# TouringMachineB1.net
KiCad netlist of a schematic drawn in EAGLE
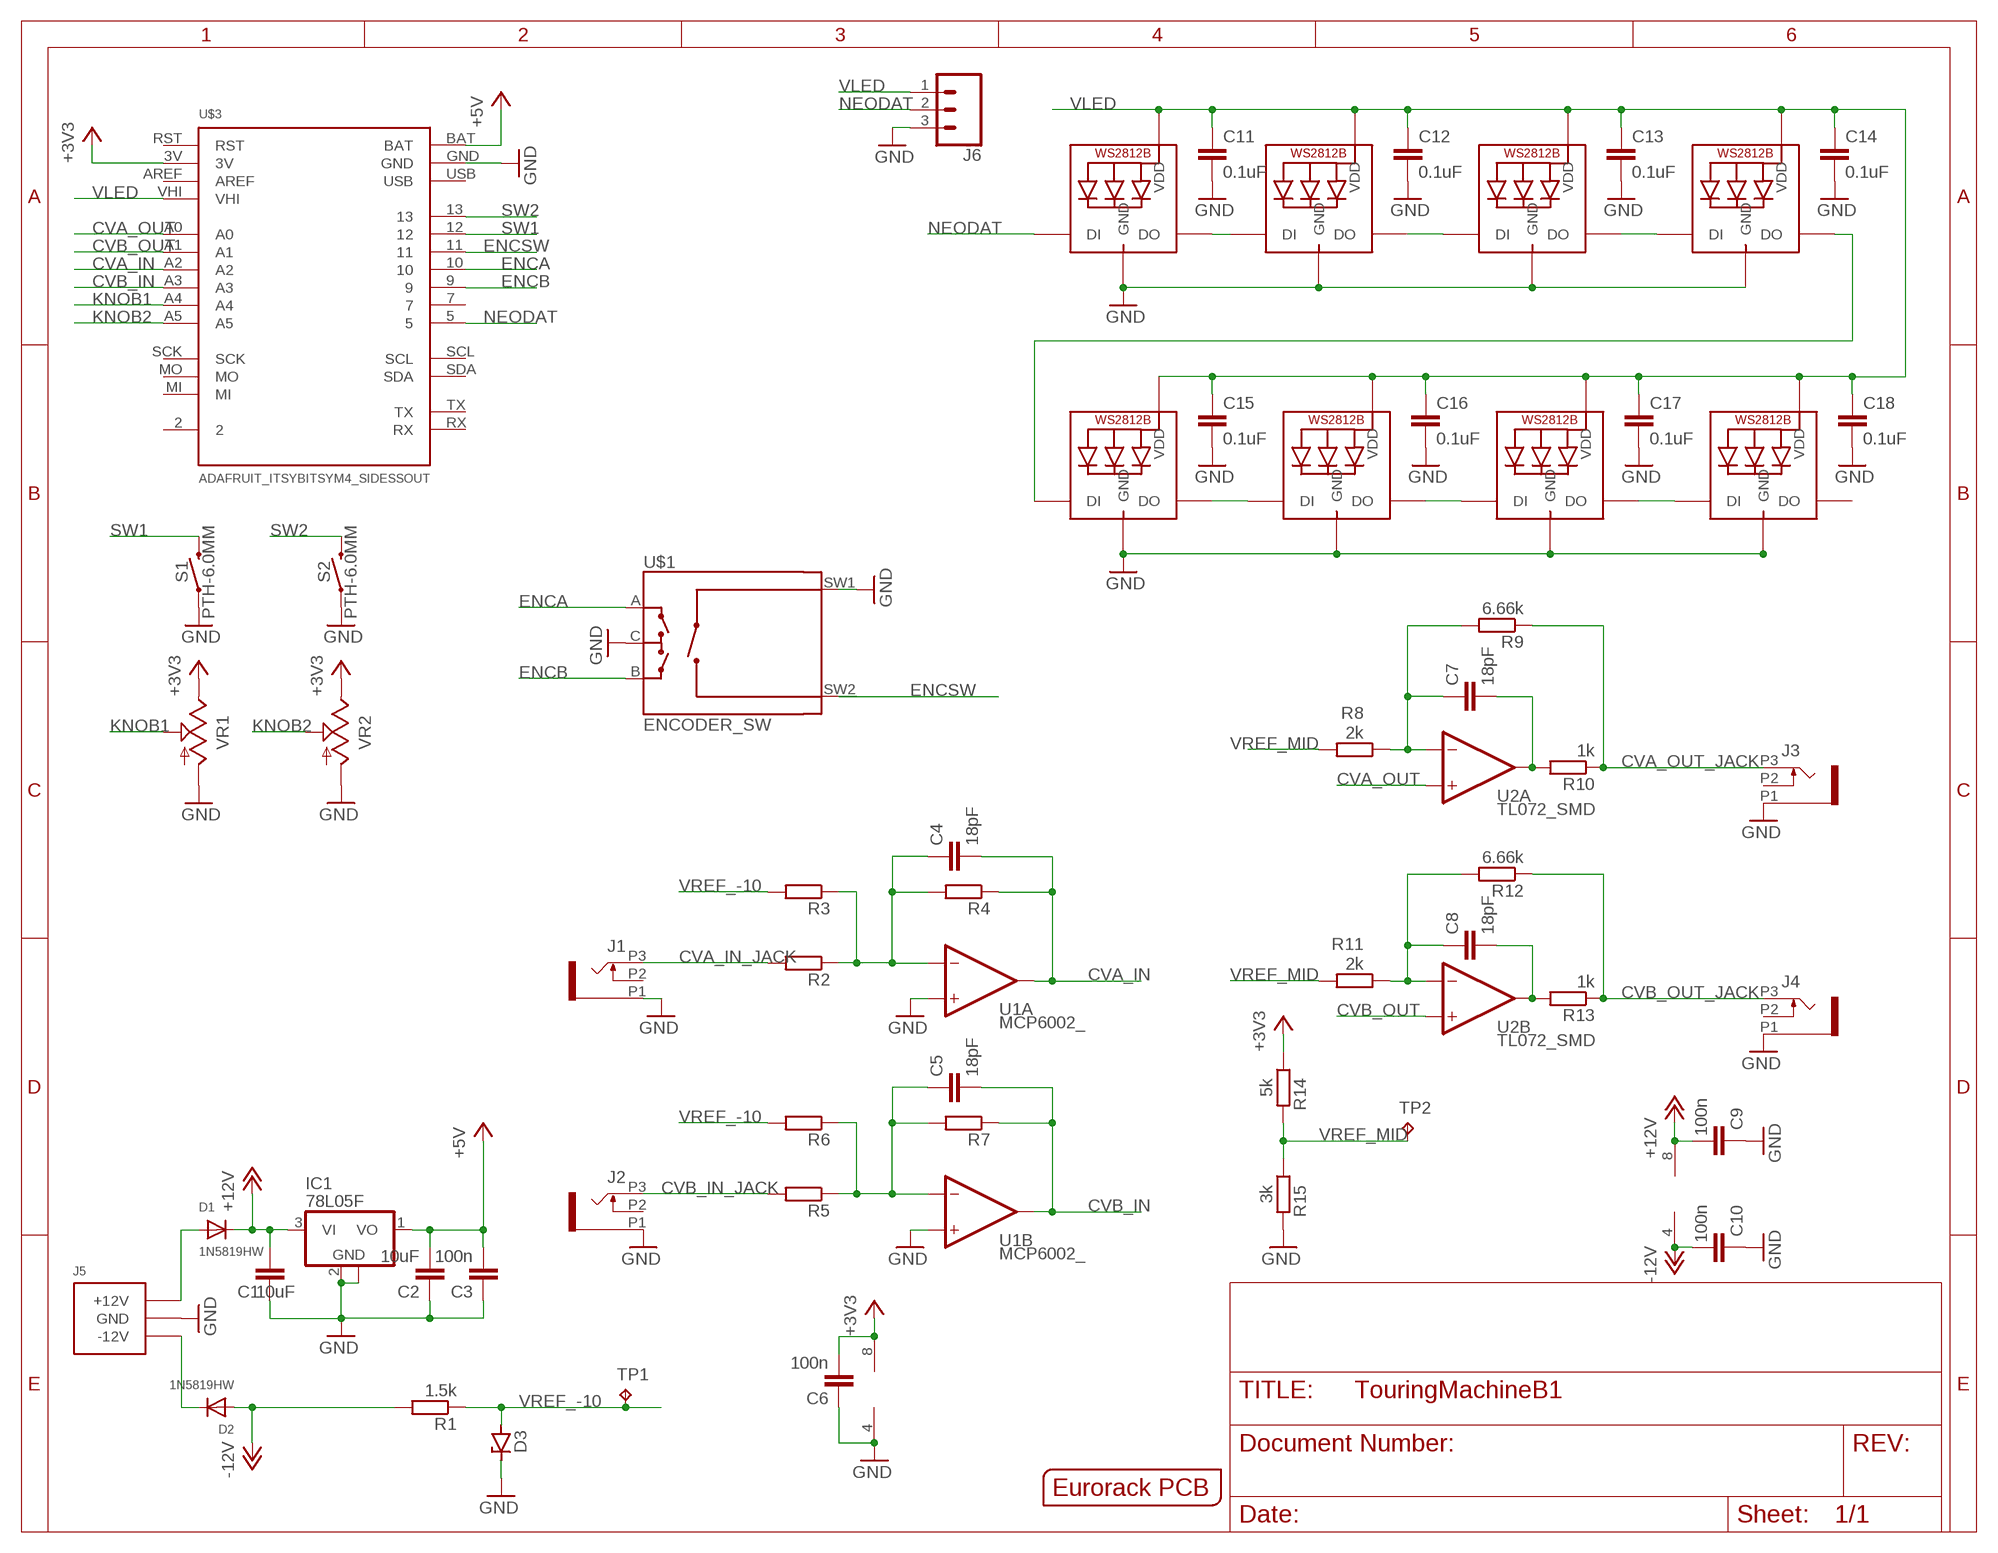
[diagram p0: schematic, sheet 1]

(export (version "E")
  (design (tool "Eeschema 10.0.6"))
  (components
    (comp (ref "C1")
      (value "10uF")
      (footprint "eagle-import:C0603")
      (libsource (lib "eagle-import") (part "C-EUC0603"))
    )
    (comp (ref "C2")
      (value "10uF")
      (footprint "eagle-import:C0603")
      (libsource (lib "eagle-import") (part "C-EUC0603"))
    )
    (comp (ref "C3")
      (value "100n")
      (footprint "eagle-import:C0603")
      (libsource (lib "eagle-import") (part "C-EUC0603"))
    )
    (comp (ref "C4")
      (value "18pF")
      (footprint "eagle-import:C0603")
      (libsource (lib "eagle-import") (part "C-EUC0603"))
    )
    (comp (ref "C5")
      (value "18pF")
      (footprint "eagle-import:C0603")
      (libsource (lib "eagle-import") (part "C-EUC0603"))
    )
    (comp (ref "C6")
      (value "100n")
      (footprint "eagle-import:C0603")
      (libsource (lib "eagle-import") (part "C-EUC0603"))
    )
    (comp (ref "C7")
      (value "18pF")
      (footprint "eagle-import:C0603")
      (libsource (lib "eagle-import") (part "C-EUC0603"))
    )
    (comp (ref "C8")
      (value "18pF")
      (footprint "eagle-import:C0603")
      (libsource (lib "eagle-import") (part "C-EUC0603"))
    )
    (comp (ref "C9")
      (value "100n")
      (footprint "eagle-import:C0603")
      (libsource (lib "eagle-import") (part "C-EUC0603"))
    )
    (comp (ref "C10")
      (value "100n")
      (footprint "eagle-import:C0603")
      (libsource (lib "eagle-import") (part "C-EUC0603"))
    )
    (comp (ref "C11")
      (value "0.1uF")
      (footprint "eagle-import:C0603")
      (libsource (lib "eagle-import") (part "C-EUC0603"))
    )
    (comp (ref "C12")
      (value "0.1uF")
      (footprint "eagle-import:C0603")
      (libsource (lib "eagle-import") (part "C-EUC0603"))
    )
    (comp (ref "C13")
      (value "0.1uF")
      (footprint "eagle-import:C0603")
      (libsource (lib "eagle-import") (part "C-EUC0603"))
    )
    (comp (ref "C14")
      (value "0.1uF")
      (footprint "eagle-import:C0603")
      (libsource (lib "eagle-import") (part "C-EUC0603"))
    )
    (comp (ref "C15")
      (value "0.1uF")
      (footprint "eagle-import:C0603")
      (libsource (lib "eagle-import") (part "C-EUC0603"))
    )
    (comp (ref "C16")
      (value "0.1uF")
      (footprint "eagle-import:C0603")
      (libsource (lib "eagle-import") (part "C-EUC0603"))
    )
    (comp (ref "C17")
      (value "0.1uF")
      (footprint "eagle-import:C0603")
      (libsource (lib "eagle-import") (part "C-EUC0603"))
    )
    (comp (ref "C18")
      (value "0.1uF")
      (footprint "eagle-import:C0603")
      (libsource (lib "eagle-import") (part "C-EUC0603"))
    )
    (comp (ref "D1")
      (value "1N5819HW")
      (footprint "eagle-import:SOD-123")
      (libsource (lib "eagle-import") (part "DIODESOD-123"))
    )
    (comp (ref "D2")
      (value "1N5819HW")
      (footprint "eagle-import:SOD-123")
      (libsource (lib "eagle-import") (part "DIODESOD-123"))
    )
    (comp (ref "D3")
      (value "ZENER-DIODESOT23")
      (footprint "eagle-import:SOT23")
      (libsource (lib "eagle-import") (part "ZENER-DIODESOT23"))
    )
    (comp (ref "IC1")
      (value "78L05F")
      (footprint "eagle-import:SOT89")
      (libsource (lib "eagle-import") (part "78LF05"))
    )
    (comp (ref "J1")
      (value "PJ301_THONKICONN6")
      (footprint "eagle-import:WQP_PJ_301M6")
      (libsource (lib "eagle-import") (part "PJ301_THONKICONN6"))
    )
    (comp (ref "J2")
      (value "PJ301_THONKICONN6")
      (footprint "eagle-import:WQP_PJ_301M6")
      (libsource (lib "eagle-import") (part "PJ301_THONKICONN6"))
    )
    (comp (ref "J3")
      (value "PJ301_THONKICONN6")
      (footprint "eagle-import:WQP_PJ_301M6")
      (libsource (lib "eagle-import") (part "PJ301_THONKICONN6"))
    )
    (comp (ref "J4")
      (value "PJ301_THONKICONN6")
      (footprint "eagle-import:WQP_PJ_301M6")
      (libsource (lib "eagle-import") (part "PJ301_THONKICONN6"))
    )
    (comp (ref "J5")
      (value "POWER_SIMPLE10-OTHERSIDE")
      (footprint "eagle-import:POWER_10_LABELSOTHERSIDE")
      (libsource (lib "eagle-import") (part "POWER_SIMPLE10-OTHERSIDE"))
    )
    (comp (ref "J6")
      (value "CONN_03")
      (footprint "eagle-import:1X03")
      (libsource (lib "eagle-import") (part "CONN_03"))
    )
    (comp (ref "LED1")
      (value "WS2812B5050")
      (footprint "eagle-import:WS2812B")
      (libsource (lib "eagle-import") (part "WS2812B5050"))
    )
    (comp (ref "LED2")
      (value "WS2812B5050")
      (footprint "eagle-import:WS2812B")
      (libsource (lib "eagle-import") (part "WS2812B5050"))
    )
    (comp (ref "LED3")
      (value "WS2812B5050")
      (footprint "eagle-import:WS2812B")
      (libsource (lib "eagle-import") (part "WS2812B5050"))
    )
    (comp (ref "LED4")
      (value "WS2812B5050")
      (footprint "eagle-import:WS2812B")
      (libsource (lib "eagle-import") (part "WS2812B5050"))
    )
    (comp (ref "LED5")
      (value "WS2812B5050")
      (footprint "eagle-import:WS2812B")
      (libsource (lib "eagle-import") (part "WS2812B5050"))
    )
    (comp (ref "LED6")
      (value "WS2812B5050")
      (footprint "eagle-import:WS2812B")
      (libsource (lib "eagle-import") (part "WS2812B5050"))
    )
    (comp (ref "LED7")
      (value "WS2812B5050")
      (footprint "eagle-import:WS2812B")
      (libsource (lib "eagle-import") (part "WS2812B5050"))
    )
    (comp (ref "LED8")
      (value "WS2812B5050")
      (footprint "eagle-import:WS2812B")
      (libsource (lib "eagle-import") (part "WS2812B5050"))
    )
    (comp (ref "PCB1")
      (value "EURORACK_PCB6HP")
      (footprint "eagle-import:EURORACK6HPPCB")
      (libsource (lib "eagle-import") (part "EURORACK_PCB6HP"))
    )
    (comp (ref "R1")
      (value "1.5k")
      (footprint "eagle-import:R0603")
      (libsource (lib "eagle-import") (part "R-EU_R0603"))
    )
    (comp (ref "R2")
      (value "R-EU_R0603")
      (footprint "eagle-import:R0603")
      (libsource (lib "eagle-import") (part "R-EU_R0603"))
    )
    (comp (ref "R3")
      (value "R-EU_R0603")
      (footprint "eagle-import:R0603")
      (libsource (lib "eagle-import") (part "R-EU_R0603"))
    )
    (comp (ref "R4")
      (value "R-EU_R0603")
      (footprint "eagle-import:R0603")
      (libsource (lib "eagle-import") (part "R-EU_R0603"))
    )
    (comp (ref "R5")
      (value "R-EU_R0603")
      (footprint "eagle-import:R0603")
      (libsource (lib "eagle-import") (part "R-EU_R0603"))
    )
    (comp (ref "R6")
      (value "R-EU_R0603")
      (footprint "eagle-import:R0603")
      (libsource (lib "eagle-import") (part "R-EU_R0603"))
    )
    (comp (ref "R7")
      (value "R-EU_R0603")
      (footprint "eagle-import:R0603")
      (libsource (lib "eagle-import") (part "R-EU_R0603"))
    )
    (comp (ref "R8")
      (value "2k")
      (footprint "eagle-import:R0603")
      (libsource (lib "eagle-import") (part "R-EU_R0603"))
    )
    (comp (ref "R9")
      (value "6.66k")
      (footprint "eagle-import:R0603")
      (libsource (lib "eagle-import") (part "R-EU_R0603"))
    )
    (comp (ref "R10")
      (value "1k")
      (footprint "eagle-import:R0603")
      (libsource (lib "eagle-import") (part "R-EU_R0603"))
    )
    (comp (ref "R11")
      (value "2k")
      (footprint "eagle-import:R0603")
      (libsource (lib "eagle-import") (part "R-EU_R0603"))
    )
    (comp (ref "R12")
      (value "6.66k")
      (footprint "eagle-import:R0603")
      (libsource (lib "eagle-import") (part "R-EU_R0603"))
    )
    (comp (ref "R13")
      (value "1k")
      (footprint "eagle-import:R0603")
      (libsource (lib "eagle-import") (part "R-EU_R0603"))
    )
    (comp (ref "R14")
      (value "5k")
      (footprint "eagle-import:R0603")
      (libsource (lib "eagle-import") (part "R-EU_R0603"))
    )
    (comp (ref "R15")
      (value "3k")
      (footprint "eagle-import:R0603")
      (libsource (lib "eagle-import") (part "R-EU_R0603"))
    )
    (comp (ref "S1")
      (value "PTH-6.0MM")
      (footprint "eagle-import:TACTILE_SWITCH_PTH_6.0MM")
      (libsource (lib "eagle-import") (part "MOMENTARY-SWITCH-SPST-PTH-6.0MM"))
    )
    (comp (ref "S2")
      (value "PTH-6.0MM")
      (footprint "eagle-import:TACTILE_SWITCH_PTH_6.0MM")
      (libsource (lib "eagle-import") (part "MOMENTARY-SWITCH-SPST-PTH-6.0MM"))
    )
    (comp (ref "TP1")
      (value "TPTP15R")
      (footprint "eagle-import:TP15R")
      (libsource (lib "eagle-import") (part "TPTP15R"))
    )
    (comp (ref "TP2")
      (value "TPTP15R")
      (footprint "eagle-import:TP15R")
      (libsource (lib "eagle-import") (part "TPTP15R"))
    )
    (comp (ref "U$1")
      (value "ENCODER_SW")
      (footprint "eagle-import:ENCODER_SW")
      (libsource (lib "eagle-import") (part "ENCODER_SW"))
    )
    (comp (ref "U$3")
      (value "ADAFRUIT_ITSYBITSYM4_SIDESSOUT")
      (footprint "eagle-import:ADAFRUIT_ITSYBITSYM4_SIDESOUT")
      (libsource (lib "eagle-import") (part "ADAFRUIT_ITSYBITSYM4_SIDESSOUT"))
    )
    (comp (ref "U1")
      (value "MCP6002_")
      (footprint "eagle-import:SO08")
      (libsource (lib "eagle-import") (part "MCP6002_"))
    )
    (comp (ref "U2")
      (value "TL072_SMD")
      (footprint "eagle-import:SO08")
      (libsource (lib "eagle-import") (part "TL072_SMD"))
    )
    (comp (ref "VR1")
      (value "9MM_SNAP-IN_POT_")
      (footprint "eagle-import:9MM_SNAP-IN_POT")
      (libsource (lib "eagle-import") (part "9MM_SNAP-IN_POT_"))
    )
    (comp (ref "VR2")
      (value "9MM_SNAP-IN_POT_")
      (footprint "eagle-import:9MM_SNAP-IN_POT")
      (libsource (lib "eagle-import") (part "9MM_SNAP-IN_POT_"))
    )
  )
  (nets
    (net (code "1") (name "+3V3") (class "Default")
      (node (ref "C6") (pin "2") (pinfunction "2_2") (pintype "passive"))
      (node (ref "R14") (pin "1") (pinfunction "1_1") (pintype "passive"))
      (node (ref "U$3") (pin "3V") (pinfunction "3V_3V") (pintype "bidirectional"))
      (node (ref "U1") (pin "8") (pinfunction "V+_8") (pintype "power_in"))
      (node (ref "VR1") (pin "3") (pinfunction "E_3") (pintype "passive"))
      (node (ref "VR2") (pin "3") (pinfunction "E_3") (pintype "passive"))
    )
    (net (code "2") (name "+5V") (class "Default")
      (node (ref "C2") (pin "2") (pinfunction "2_2") (pintype "passive"))
      (node (ref "C3") (pin "2") (pinfunction "2_2") (pintype "passive"))
      (node (ref "IC1") (pin "1") (pinfunction "VO_1") (pintype "passive"))
      (node (ref "U$3") (pin "BAT") (pinfunction "BAT_BAT") (pintype "bidirectional"))
    )
    (net (code "3") (name "+12V") (class "Default")
      (node (ref "C1") (pin "2") (pinfunction "2_2") (pintype "passive"))
      (node (ref "C9") (pin "2") (pinfunction "2_2") (pintype "passive"))
      (node (ref "D1") (pin "C") (pinfunction "C_C") (pintype "passive"))
      (node (ref "IC1") (pin "3") (pinfunction "VI_3") (pintype "input"))
      (node (ref "U2") (pin "8") (pinfunction "V+_8") (pintype "power_in"))
    )
    (net (code "4") (name "-12V") (class "Default")
      (node (ref "C10") (pin "2") (pinfunction "2_2") (pintype "passive"))
      (node (ref "D2") (pin "A") (pinfunction "A_A") (pintype "passive"))
      (node (ref "R1") (pin "2") (pinfunction "2_2") (pintype "passive"))
      (node (ref "U2") (pin "4") (pinfunction "V-_4") (pintype "power_in"))
    )
    (net (code "5") (name "/CVA_IN") (class "Default")
      (node (ref "C4") (pin "2") (pinfunction "2_2") (pintype "passive"))
      (node (ref "R4") (pin "1") (pinfunction "1_1") (pintype "passive"))
      (node (ref "U$3") (pin "A2") (pinfunction "A2_A2") (pintype "bidirectional"))
      (node (ref "U1") (pin "1") (pinfunction "OUT_1") (pintype "output"))
    )
    (net (code "6") (name "/CVA_IN_JACK") (class "Default")
      (node (ref "J1") (pin "P3") (pinfunction "3_P3") (pintype "passive"))
      (node (ref "R2") (pin "2") (pinfunction "2_2") (pintype "passive"))
    )
    (net (code "7") (name "/CVA_OUT") (class "Default")
      (node (ref "U$3") (pin "A0") (pinfunction "A0_A0") (pintype "bidirectional"))
      (node (ref "U2") (pin "3") (pinfunction "+IN_3") (pintype "input"))
    )
    (net (code "8") (name "/CVA_OUT_JACK") (class "Default")
      (node (ref "J3") (pin "P3") (pinfunction "3_P3") (pintype "passive"))
      (node (ref "R10") (pin "1") (pinfunction "1_1") (pintype "passive"))
      (node (ref "R9") (pin "1") (pinfunction "1_1") (pintype "passive"))
    )
    (net (code "9") (name "/CVB_IN") (class "Default")
      (node (ref "C5") (pin "2") (pinfunction "2_2") (pintype "passive"))
      (node (ref "R7") (pin "1") (pinfunction "1_1") (pintype "passive"))
      (node (ref "U$3") (pin "A3") (pinfunction "A3_A3") (pintype "bidirectional"))
      (node (ref "U1") (pin "7") (pinfunction "OUT_7") (pintype "output"))
    )
    (net (code "10") (name "/CVB_IN_JACK") (class "Default")
      (node (ref "J2") (pin "P3") (pinfunction "3_P3") (pintype "passive"))
      (node (ref "R5") (pin "2") (pinfunction "2_2") (pintype "passive"))
    )
    (net (code "11") (name "/CVB_OUT") (class "Default")
      (node (ref "U$3") (pin "A1") (pinfunction "A1_A1") (pintype "bidirectional"))
      (node (ref "U2") (pin "5") (pinfunction "+IN_5") (pintype "input"))
    )
    (net (code "12") (name "/CVB_OUT_JACK") (class "Default")
      (node (ref "J4") (pin "P3") (pinfunction "3_P3") (pintype "passive"))
      (node (ref "R12") (pin "1") (pinfunction "1_1") (pintype "passive"))
      (node (ref "R13") (pin "1") (pinfunction "1_1") (pintype "passive"))
    )
    (net (code "13") (name "/ENCA") (class "Default")
      (node (ref "U$1") (pin "A") (pinfunction "A_A") (pintype "bidirectional"))
      (node (ref "U$3") (pin "10") (pinfunction "10_10") (pintype "bidirectional"))
    )
    (net (code "14") (name "/ENCB") (class "Default")
      (node (ref "U$1") (pin "B") (pinfunction "B_B") (pintype "bidirectional"))
      (node (ref "U$3") (pin "9") (pinfunction "9_9") (pintype "bidirectional"))
    )
    (net (code "15") (name "/ENCSW") (class "Default")
      (node (ref "U$1") (pin "SW2") (pinfunction "SW2_SW2") (pintype "passive"))
      (node (ref "U$3") (pin "11") (pinfunction "11_11") (pintype "bidirectional"))
    )
    (net (code "16") (name "/KNOB1") (class "Default")
      (node (ref "U$3") (pin "A4") (pinfunction "A4_A4") (pintype "bidirectional"))
      (node (ref "VR1") (pin "2") (pinfunction "S_2") (pintype "passive"))
    )
    (net (code "17") (name "/KNOB2") (class "Default")
      (node (ref "U$3") (pin "A5") (pinfunction "A5_A5") (pintype "bidirectional"))
      (node (ref "VR2") (pin "2") (pinfunction "S_2") (pintype "passive"))
    )
    (net (code "18") (name "/NEODAT") (class "Default")
      (node (ref "J6") (pin "2") (pinfunction "2_2") (pintype "passive"))
      (node (ref "LED1") (pin "4-DIN") (pinfunction "DI_4-DIN") (pintype "input"))
      (node (ref "U$3") (pin "5") (pinfunction "5_5") (pintype "bidirectional"))
    )
    (net (code "19") (name "/SW1") (class "Default")
      (node (ref "S1") (pin "3") (pinfunction "2_3") (pintype "passive"))
      (node (ref "U$3") (pin "12") (pinfunction "12_12") (pintype "bidirectional"))
    )
    (net (code "20") (name "/SW2") (class "Default")
      (node (ref "S2") (pin "3") (pinfunction "2_3") (pintype "passive"))
      (node (ref "U$3") (pin "13") (pinfunction "13_13") (pintype "bidirectional"))
    )
    (net (code "21") (name "/VLED") (class "Default")
      (node (ref "C11") (pin "1") (pinfunction "1_1") (pintype "passive"))
      (node (ref "C12") (pin "1") (pinfunction "1_1") (pintype "passive"))
      (node (ref "C13") (pin "1") (pinfunction "1_1") (pintype "passive"))
      (node (ref "C14") (pin "1") (pinfunction "1_1") (pintype "passive"))
      (node (ref "C15") (pin "1") (pinfunction "1_1") (pintype "passive"))
      (node (ref "C16") (pin "1") (pinfunction "1_1") (pintype "passive"))
      (node (ref "C17") (pin "1") (pinfunction "1_1") (pintype "passive"))
      (node (ref "C18") (pin "1") (pinfunction "1_1") (pintype "passive"))
      (node (ref "J6") (pin "1") (pinfunction "1_1") (pintype "passive"))
      (node (ref "LED1") (pin "1-VDD") (pinfunction "VDD_1-VDD") (pintype "power_in"))
      (node (ref "LED2") (pin "1-VDD") (pinfunction "VDD_1-VDD") (pintype "power_in"))
      (node (ref "LED3") (pin "1-VDD") (pinfunction "VDD_1-VDD") (pintype "power_in"))
      (node (ref "LED4") (pin "1-VDD") (pinfunction "VDD_1-VDD") (pintype "power_in"))
      (node (ref "LED5") (pin "1-VDD") (pinfunction "VDD_1-VDD") (pintype "power_in"))
      (node (ref "LED6") (pin "1-VDD") (pinfunction "VDD_1-VDD") (pintype "power_in"))
      (node (ref "LED7") (pin "1-VDD") (pinfunction "VDD_1-VDD") (pintype "power_in"))
      (node (ref "LED8") (pin "1-VDD") (pinfunction "VDD_1-VDD") (pintype "power_in"))
      (node (ref "U$3") (pin "VHI") (pinfunction "VHI_VHI") (pintype "bidirectional"))
    )
    (net (code "22") (name "/VREF_-10") (class "Default")
      (node (ref "D3") (pin "1") (pinfunction "A_1") (pintype "passive"))
      (node (ref "R1") (pin "1") (pinfunction "1_1") (pintype "passive"))
      (node (ref "R3") (pin "2") (pinfunction "2_2") (pintype "passive"))
      (node (ref "R6") (pin "2") (pinfunction "2_2") (pintype "passive"))
      (node (ref "TP1") (pin "TP") (pinfunction "TP_TP") (pintype "input"))
    )
    (net (code "23") (name "/VREF_MID") (class "Default")
      (node (ref "R11") (pin "2") (pinfunction "2_2") (pintype "passive"))
      (node (ref "R14") (pin "2") (pinfunction "2_2") (pintype "passive"))
      (node (ref "R15") (pin "1") (pinfunction "1_1") (pintype "passive"))
      (node (ref "R8") (pin "2") (pinfunction "2_2") (pintype "passive"))
      (node (ref "TP2") (pin "TP") (pinfunction "TP_TP") (pintype "input"))
    )
    (net (code "24") (name "GND") (class "Default")
      (node (ref "C1") (pin "1") (pinfunction "1_1") (pintype "passive"))
      (node (ref "C10") (pin "1") (pinfunction "1_1") (pintype "passive"))
      (node (ref "C11") (pin "2") (pinfunction "2_2") (pintype "passive"))
      (node (ref "C12") (pin "2") (pinfunction "2_2") (pintype "passive"))
      (node (ref "C13") (pin "2") (pinfunction "2_2") (pintype "passive"))
      (node (ref "C14") (pin "2") (pinfunction "2_2") (pintype "passive"))
      (node (ref "C15") (pin "2") (pinfunction "2_2") (pintype "passive"))
      (node (ref "C16") (pin "2") (pinfunction "2_2") (pintype "passive"))
      (node (ref "C17") (pin "2") (pinfunction "2_2") (pintype "passive"))
      (node (ref "C18") (pin "2") (pinfunction "2_2") (pintype "passive"))
      (node (ref "C2") (pin "1") (pinfunction "1_1") (pintype "passive"))
      (node (ref "C3") (pin "1") (pinfunction "1_1") (pintype "passive"))
      (node (ref "C6") (pin "1") (pinfunction "1_1") (pintype "passive"))
      (node (ref "C9") (pin "1") (pinfunction "1_1") (pintype "passive"))
      (node (ref "D3") (pin "3") (pinfunction "C_3") (pintype "passive"))
      (node (ref "IC1") (pin "2") (pinfunction "GND_2") (pintype "passive"))
      (node (ref "IC1") (pin "2@1") (pinfunction "GND_2@1") (pintype "passive"))
      (node (ref "J1") (pin "P1") (pinfunction "1_P1") (pintype "passive"))
      (node (ref "J2") (pin "P1") (pinfunction "1_P1") (pintype "passive"))
      (node (ref "J3") (pin "P1") (pinfunction "1_P1") (pintype "passive"))
      (node (ref "J4") (pin "P1") (pinfunction "1_P1") (pintype "passive"))
      (node (ref "J5") (pin "3") (pinfunction "GND_3") (pintype "bidirectional"))
      (node (ref "J5") (pin "4") (pinfunction "GND_4") (pintype "bidirectional"))
      (node (ref "J5") (pin "5") (pinfunction "GND_5") (pintype "bidirectional"))
      (node (ref "J5") (pin "6") (pinfunction "GND_6") (pintype "bidirectional"))
      (node (ref "J5") (pin "7") (pinfunction "GND_7") (pintype "bidirectional"))
      (node (ref "J5") (pin "8") (pinfunction "GND_8") (pintype "bidirectional"))
      (node (ref "J6") (pin "3") (pinfunction "3_3") (pintype "passive"))
      (node (ref "LED1") (pin "3-GND") (pinfunction "GND_3-GND") (pintype "power_in"))
      (node (ref "LED2") (pin "3-GND") (pinfunction "GND_3-GND") (pintype "power_in"))
      (node (ref "LED3") (pin "3-GND") (pinfunction "GND_3-GND") (pintype "power_in"))
      (node (ref "LED4") (pin "3-GND") (pinfunction "GND_3-GND") (pintype "power_in"))
      (node (ref "LED5") (pin "3-GND") (pinfunction "GND_3-GND") (pintype "power_in"))
      (node (ref "LED6") (pin "3-GND") (pinfunction "GND_3-GND") (pintype "power_in"))
      (node (ref "LED7") (pin "3-GND") (pinfunction "GND_3-GND") (pintype "power_in"))
      (node (ref "LED8") (pin "3-GND") (pinfunction "GND_3-GND") (pintype "power_in"))
      (node (ref "R15") (pin "2") (pinfunction "2_2") (pintype "passive"))
      (node (ref "S1") (pin "1") (pinfunction "1_1") (pintype "passive"))
      (node (ref "S2") (pin "1") (pinfunction "1_1") (pintype "passive"))
      (node (ref "U$1") (pin "C") (pinfunction "C_C") (pintype "bidirectional"))
      (node (ref "U$1") (pin "SW1") (pinfunction "SW1_SW1") (pintype "passive"))
      (node (ref "U$3") (pin "GND") (pinfunction "GND_GND") (pintype "bidirectional"))
      (node (ref "U1") (pin "3") (pinfunction "+IN_3") (pintype "input"))
      (node (ref "U1") (pin "4") (pinfunction "V-_4") (pintype "power_in"))
      (node (ref "U1") (pin "5") (pinfunction "+IN_5") (pintype "input"))
      (node (ref "VR1") (pin "1") (pinfunction "A_1") (pintype "passive"))
      (node (ref "VR2") (pin "1") (pinfunction "A_1") (pintype "passive"))
    )
    (net (code "25") (name "Net-(D1-PadA)") (class "Default")
      (node (ref "D1") (pin "A") (pinfunction "A_A") (pintype "passive"))
      (node (ref "J5") (pin "10") (pinfunction "+12V_10") (pintype "bidirectional"))
      (node (ref "J5") (pin "9") (pinfunction "+12V_9") (pintype "bidirectional"))
    )
    (net (code "26") (name "Net-(D2-PadC)") (class "Default")
      (node (ref "D2") (pin "C") (pinfunction "C_C") (pintype "passive"))
      (node (ref "J5") (pin "1") (pinfunction "-12V_1") (pintype "bidirectional"))
      (node (ref "J5") (pin "2") (pinfunction "-12V_2") (pintype "bidirectional"))
    )
    (net (code "27") (name "Net-(LED1-DO)") (class "Default")
      (node (ref "LED1") (pin "2-DOUT") (pinfunction "DO_2-DOUT") (pintype "output"))
      (node (ref "LED2") (pin "4-DIN") (pinfunction "DI_4-DIN") (pintype "input"))
    )
    (net (code "28") (name "Net-(LED2-DO)") (class "Default")
      (node (ref "LED2") (pin "2-DOUT") (pinfunction "DO_2-DOUT") (pintype "output"))
      (node (ref "LED3") (pin "4-DIN") (pinfunction "DI_4-DIN") (pintype "input"))
    )
    (net (code "29") (name "Net-(LED3-DO)") (class "Default")
      (node (ref "LED3") (pin "2-DOUT") (pinfunction "DO_2-DOUT") (pintype "output"))
      (node (ref "LED4") (pin "4-DIN") (pinfunction "DI_4-DIN") (pintype "input"))
    )
    (net (code "30") (name "Net-(LED4-DO)") (class "Default")
      (node (ref "LED4") (pin "2-DOUT") (pinfunction "DO_2-DOUT") (pintype "output"))
      (node (ref "LED5") (pin "4-DIN") (pinfunction "DI_4-DIN") (pintype "input"))
    )
    (net (code "31") (name "Net-(LED5-DO)") (class "Default")
      (node (ref "LED5") (pin "2-DOUT") (pinfunction "DO_2-DOUT") (pintype "output"))
      (node (ref "LED6") (pin "4-DIN") (pinfunction "DI_4-DIN") (pintype "input"))
    )
    (net (code "32") (name "Net-(LED6-DO)") (class "Default")
      (node (ref "LED6") (pin "2-DOUT") (pinfunction "DO_2-DOUT") (pintype "output"))
      (node (ref "LED7") (pin "4-DIN") (pinfunction "DI_4-DIN") (pintype "input"))
    )
    (net (code "33") (name "Net-(LED7-DO)") (class "Default")
      (node (ref "LED7") (pin "2-DOUT") (pinfunction "DO_2-DOUT") (pintype "output"))
      (node (ref "LED8") (pin "4-DIN") (pinfunction "DI_4-DIN") (pintype "input"))
    )
    (net (code "34") (name "Net-(U1A--IN)") (class "Default")
      (node (ref "C4") (pin "1") (pinfunction "1_1") (pintype "passive"))
      (node (ref "R2") (pin "1") (pinfunction "1_1") (pintype "passive"))
      (node (ref "R3") (pin "1") (pinfunction "1_1") (pintype "passive"))
      (node (ref "R4") (pin "2") (pinfunction "2_2") (pintype "passive"))
      (node (ref "U1") (pin "2") (pinfunction "-IN_2") (pintype "input"))
    )
    (net (code "35") (name "Net-(U1B--IN)") (class "Default")
      (node (ref "C5") (pin "1") (pinfunction "1_1") (pintype "passive"))
      (node (ref "R5") (pin "1") (pinfunction "1_1") (pintype "passive"))
      (node (ref "R6") (pin "1") (pinfunction "1_1") (pintype "passive"))
      (node (ref "R7") (pin "2") (pinfunction "2_2") (pintype "passive"))
      (node (ref "U1") (pin "6") (pinfunction "-IN_6") (pintype "input"))
    )
    (net (code "36") (name "Net-(U2A--IN)") (class "Default")
      (node (ref "C7") (pin "1") (pinfunction "1_1") (pintype "passive"))
      (node (ref "R8") (pin "1") (pinfunction "1_1") (pintype "passive"))
      (node (ref "R9") (pin "2") (pinfunction "2_2") (pintype "passive"))
      (node (ref "U2") (pin "2") (pinfunction "-IN_2") (pintype "input"))
    )
    (net (code "37") (name "Net-(U2A-OUT)") (class "Default")
      (node (ref "C7") (pin "2") (pinfunction "2_2") (pintype "passive"))
      (node (ref "R10") (pin "2") (pinfunction "2_2") (pintype "passive"))
      (node (ref "U2") (pin "1") (pinfunction "OUT_1") (pintype "output"))
    )
    (net (code "38") (name "Net-(U2B--IN)") (class "Default")
      (node (ref "C8") (pin "1") (pinfunction "1_1") (pintype "passive"))
      (node (ref "R11") (pin "1") (pinfunction "1_1") (pintype "passive"))
      (node (ref "R12") (pin "2") (pinfunction "2_2") (pintype "passive"))
      (node (ref "U2") (pin "6") (pinfunction "-IN_6") (pintype "input"))
    )
    (net (code "39") (name "Net-(U2B-OUT)") (class "Default")
      (node (ref "C8") (pin "2") (pinfunction "2_2") (pintype "passive"))
      (node (ref "R13") (pin "2") (pinfunction "2_2") (pintype "passive"))
      (node (ref "U2") (pin "7") (pinfunction "OUT_7") (pintype "output"))
    )
    (net (code "40") (name "unconnected-(J1-2-PadP2)") (class "Default")
      (node (ref "J1") (pin "P2") (pinfunction "2_P2") (pintype "passive"))
    )
    (net (code "41") (name "unconnected-(J2-2-PadP2)") (class "Default")
      (node (ref "J2") (pin "P2") (pinfunction "2_P2") (pintype "passive"))
    )
    (net (code "42") (name "unconnected-(J3-2-PadP2)") (class "Default")
      (node (ref "J3") (pin "P2") (pinfunction "2_P2") (pintype "passive"))
    )
    (net (code "43") (name "unconnected-(J4-2-PadP2)") (class "Default")
      (node (ref "J4") (pin "P2") (pinfunction "2_P2") (pintype "passive"))
    )
    (net (code "44") (name "unconnected-(LED8-DO-Pad2-DOUT)") (class "Default")
      (node (ref "LED8") (pin "2-DOUT") (pinfunction "DO_2-DOUT") (pintype "output"))
    )
    (net (code "45") (name "unconnected-(U$3-Pad2)") (class "Default")
      (node (ref "U$3") (pin "2") (pinfunction "2_2") (pintype "bidirectional"))
    )
    (net (code "46") (name "unconnected-(U$3-Pad7)") (class "Default")
      (node (ref "U$3") (pin "7") (pinfunction "7_7") (pintype "bidirectional"))
    )
    (net (code "47") (name "unconnected-(U$3-PadAREF)") (class "Default")
      (node (ref "U$3") (pin "AREF") (pinfunction "AREF_AREF") (pintype "bidirectional"))
    )
    (net (code "48") (name "unconnected-(U$3-PadMI)") (class "Default")
      (node (ref "U$3") (pin "MI") (pinfunction "MI_MI") (pintype "bidirectional"))
    )
    (net (code "49") (name "unconnected-(U$3-PadMO)") (class "Default")
      (node (ref "U$3") (pin "MO") (pinfunction "MO_MO") (pintype "bidirectional"))
    )
    (net (code "50") (name "unconnected-(U$3-PadRST)") (class "Default")
      (node (ref "U$3") (pin "RST") (pinfunction "RST_RST") (pintype "bidirectional"))
    )
    (net (code "51") (name "unconnected-(U$3-PadRX)") (class "Default")
      (node (ref "U$3") (pin "RX") (pinfunction "RX_RX") (pintype "bidirectional"))
    )
    (net (code "52") (name "unconnected-(U$3-PadSCK)") (class "Default")
      (node (ref "U$3") (pin "SCK") (pinfunction "SCK_SCK") (pintype "bidirectional"))
    )
    (net (code "53") (name "unconnected-(U$3-PadSCL)") (class "Default")
      (node (ref "U$3") (pin "SCL") (pinfunction "SCL_SCL") (pintype "bidirectional"))
    )
    (net (code "54") (name "unconnected-(U$3-PadSDA)") (class "Default")
      (node (ref "U$3") (pin "SDA") (pinfunction "SDA_SDA") (pintype "bidirectional"))
    )
    (net (code "55") (name "unconnected-(U$3-PadTX)") (class "Default")
      (node (ref "U$3") (pin "TX") (pinfunction "TX_TX") (pintype "bidirectional"))
    )
    (net (code "56") (name "unconnected-(U$3-PadUSB)") (class "Default")
      (node (ref "U$3") (pin "USB") (pinfunction "USB_USB") (pintype "bidirectional"))
    )
  )
)
